# RF_Amplifier.net
KiCad netlist of a schematic drawn in Altium Designer
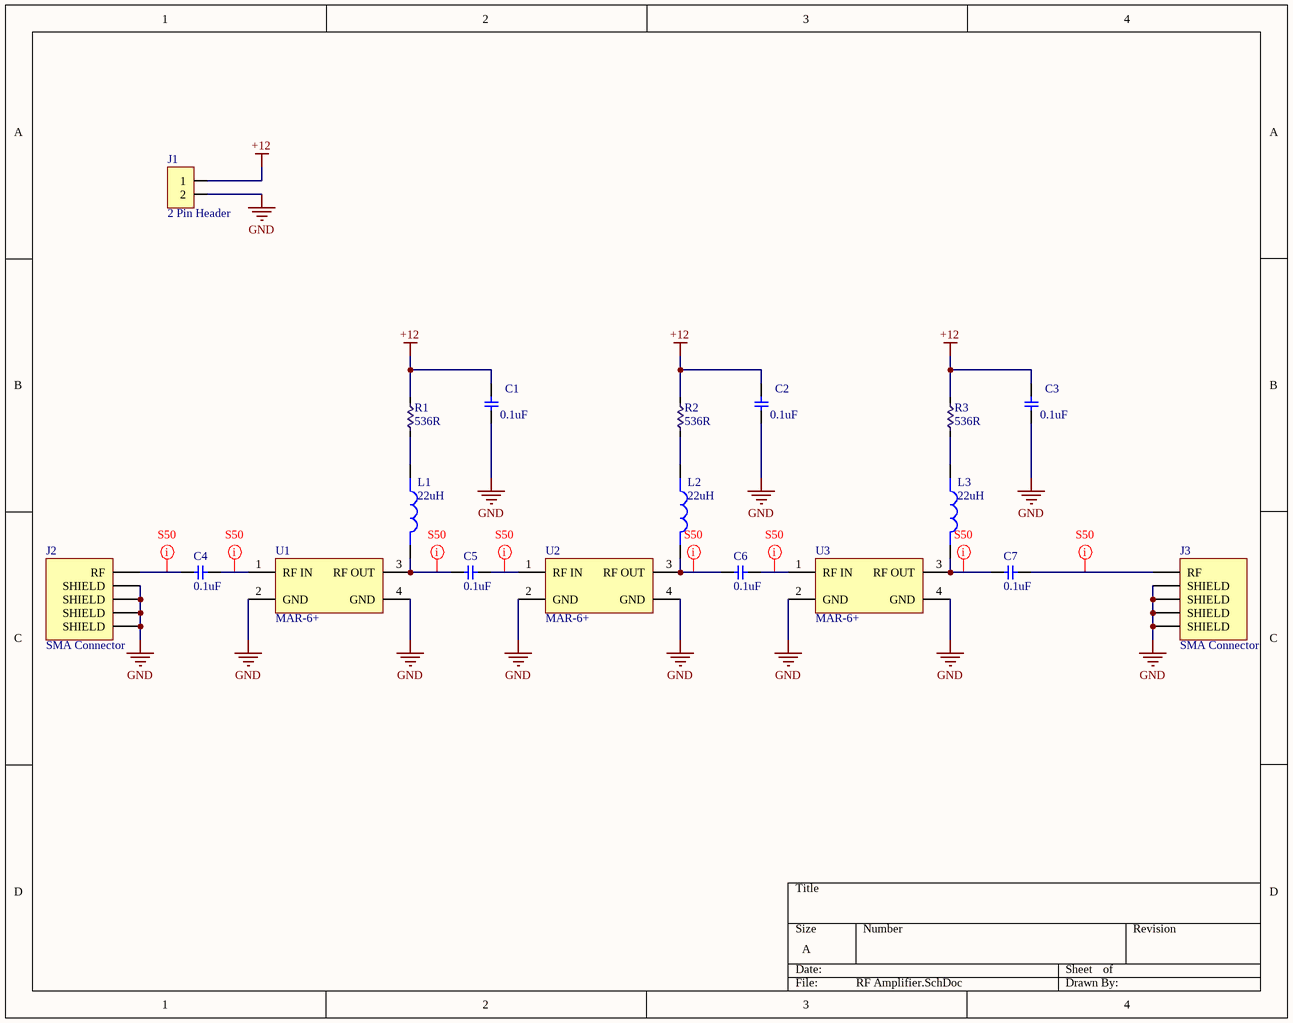
[diagram p0: RF Amplifier.SchDoc]

(export (version "E")
  (design (tool "Eeschema 10.0.6"))
  (components
    (comp (ref "C1") (value "0.1uF") (footprint "CAP805") (libsource (lib "Schlib1") (part "Cap")))
    (comp (ref "C2") (value "0.1uF") (footprint "CAP805") (libsource (lib "Schlib1") (part "Cap")))
    (comp (ref "C3") (value "0.1uF") (footprint "CAP805") (libsource (lib "Schlib1") (part "Cap")))
    (comp (ref "C4") (value "0.1uF") (footprint "CAP805") (libsource (lib "Schlib1") (part "Cap")))
    (comp (ref "C5") (value "0.1uF") (footprint "CAP805") (libsource (lib "Schlib1") (part "Cap")))
    (comp (ref "C6") (value "0.1uF") (footprint "CAP805") (libsource (lib "Schlib1") (part "Cap")))
    (comp (ref "C7") (value "0.1uF") (footprint "CAP805") (libsource (lib "Schlib1") (part "Cap")))
    (comp (ref "J1")
      (value "2 Pin Header")
      (footprint "Connector_2POS_2.54mm")
      (libsource (lib "Schematic_Library") (part "2 Pin Header"))
    )
    (comp (ref "J2")
      (value "SMA Connector")
      (footprint "Molex 73251-1150")
      (libsource (lib "Schematic_Library") (part "SMA Connector"))
    )
    (comp (ref "J3")
      (value "SMA Connector")
      (footprint "Molex 73251-1150")
      (libsource (lib "") (part "SMA Connector_1"))
    )
    (comp (ref "L1")
      (value "22uH")
      (footprint "INDUCtOR_SMD_4.2x4.4")
      (libsource (lib "Schlib1") (part "Inductor"))
    )
    (comp (ref "L2")
      (value "22uH")
      (footprint "INDUCtOR_SMD_4.2x4.4")
      (libsource (lib "Schlib1") (part "Inductor"))
    )
    (comp (ref "L3")
      (value "22uH")
      (footprint "INDUCtOR_SMD_4.2x4.4")
      (libsource (lib "Schlib1") (part "Inductor"))
    )
    (comp (ref "R1") (value "536R") (footprint "RES1812") (libsource (lib "Schlib1") (part "Res")))
    (comp (ref "R2") (value "536R") (footprint "RES1812") (libsource (lib "Schlib1") (part "Res")))
    (comp (ref "R3") (value "536R") (footprint "RES1812") (libsource (lib "Schlib1") (part "Res")))
    (comp (ref "U1") (value "MAR-6+") (footprint "VV105") (libsource (lib "Schlib1") (part "MAR-6+")))
    (comp (ref "U2") (value "MAR-6+") (footprint "VV105") (libsource (lib "Schlib1") (part "MAR-6+")))
    (comp (ref "U3") (value "MAR-6+") (footprint "VV105") (libsource (lib "Schlib1") (part "MAR-6+")))
  )
  (nets
    (net (code "1") (name "+12") (class "Default")
      (node (ref "C1") (pin "2") (pinfunction "2_2") (pintype "passive"))
      (node (ref "C2") (pin "2") (pinfunction "2_2") (pintype "passive"))
      (node (ref "C3") (pin "2") (pinfunction "2_2") (pintype "passive"))
      (node (ref "J1") (pin "1") (pinfunction "1_1") (pintype "passive"))
      (node (ref "R1") (pin "2") (pinfunction "2_2") (pintype "passive"))
      (node (ref "R2") (pin "2") (pinfunction "2_2") (pintype "passive"))
      (node (ref "R3") (pin "2") (pinfunction "2_2") (pintype "passive"))
    )
    (net (code "2") (name "GND") (class "Default")
      (node (ref "C1") (pin "1") (pinfunction "1_1") (pintype "passive"))
      (node (ref "C2") (pin "1") (pinfunction "1_1") (pintype "passive"))
      (node (ref "C3") (pin "1") (pinfunction "1_1") (pintype "passive"))
      (node (ref "J1") (pin "2") (pinfunction "2_2") (pintype "passive"))
      (node (ref "J2") (pin "2") (pinfunction "SHIELD_2") (pintype "passive"))
      (node (ref "J2") (pin "3") (pinfunction "SHIELD_3") (pintype "passive"))
      (node (ref "J2") (pin "4") (pinfunction "SHIELD_4") (pintype "passive"))
      (node (ref "J2") (pin "5") (pinfunction "SHIELD_5") (pintype "passive"))
      (node (ref "J3") (pin "2") (pinfunction "SHIELD_2") (pintype "passive"))
      (node (ref "J3") (pin "3") (pinfunction "SHIELD_3") (pintype "passive"))
      (node (ref "J3") (pin "4") (pinfunction "SHIELD_4") (pintype "passive"))
      (node (ref "J3") (pin "5") (pinfunction "SHIELD_5") (pintype "passive"))
      (node (ref "U1") (pin "2") (pinfunction "GND_2") (pintype "passive"))
      (node (ref "U1") (pin "4") (pinfunction "GND_4") (pintype "passive"))
      (node (ref "U2") (pin "2") (pinfunction "GND_2") (pintype "passive"))
      (node (ref "U2") (pin "4") (pinfunction "GND_4") (pintype "passive"))
      (node (ref "U3") (pin "2") (pinfunction "GND_2") (pintype "passive"))
      (node (ref "U3") (pin "4") (pinfunction "GND_4") (pintype "passive"))
    )
    (net (code "3") (name "Net-(J2-RF)") (class "Default")
      (node (ref "C4") (pin "1") (pinfunction "1_1") (pintype "passive"))
      (node (ref "J2") (pin "1") (pinfunction "RF_1") (pintype "passive"))
    )
    (net (code "4") (name "Net-(J3-RF)") (class "Default")
      (node (ref "C7") (pin "2") (pinfunction "2_2") (pintype "passive"))
      (node (ref "J3") (pin "1") (pinfunction "RF_1") (pintype "passive"))
    )
    (net (code "5") (name "Net-(L1-Pad1)") (class "Default")
      (node (ref "L1") (pin "1") (pinfunction "1_1") (pintype "passive"))
      (node (ref "R1") (pin "1") (pinfunction "1_1") (pintype "passive"))
    )
    (net (code "6") (name "Net-(L2-Pad1)") (class "Default")
      (node (ref "L2") (pin "1") (pinfunction "1_1") (pintype "passive"))
      (node (ref "R2") (pin "1") (pinfunction "1_1") (pintype "passive"))
    )
    (net (code "7") (name "Net-(L3-Pad1)") (class "Default")
      (node (ref "L3") (pin "1") (pinfunction "1_1") (pintype "passive"))
      (node (ref "R3") (pin "1") (pinfunction "1_1") (pintype "passive"))
    )
    (net (code "8") (name "Net-(U1-RF_IN)") (class "Default")
      (node (ref "C4") (pin "2") (pinfunction "2_2") (pintype "passive"))
      (node (ref "U1") (pin "1") (pinfunction "RF_IN_1") (pintype "passive"))
    )
    (net (code "9") (name "Net-(U1-RF_OUT)") (class "Default")
      (node (ref "C5") (pin "1") (pinfunction "1_1") (pintype "passive"))
      (node (ref "L1") (pin "2") (pinfunction "2_2") (pintype "passive"))
      (node (ref "U1") (pin "3") (pinfunction "RF_OUT_3") (pintype "passive"))
    )
    (net (code "10") (name "Net-(U2-RF_IN)") (class "Default")
      (node (ref "C5") (pin "2") (pinfunction "2_2") (pintype "passive"))
      (node (ref "U2") (pin "1") (pinfunction "RF_IN_1") (pintype "passive"))
    )
    (net (code "11") (name "Net-(U2-RF_OUT)") (class "Default")
      (node (ref "C6") (pin "1") (pinfunction "1_1") (pintype "passive"))
      (node (ref "L2") (pin "2") (pinfunction "2_2") (pintype "passive"))
      (node (ref "U2") (pin "3") (pinfunction "RF_OUT_3") (pintype "passive"))
    )
    (net (code "12") (name "Net-(U3-RF_IN)") (class "Default")
      (node (ref "C6") (pin "2") (pinfunction "2_2") (pintype "passive"))
      (node (ref "U3") (pin "1") (pinfunction "RF_IN_1") (pintype "passive"))
    )
    (net (code "13") (name "Net-(U3-RF_OUT)") (class "Default")
      (node (ref "C7") (pin "1") (pinfunction "1_1") (pintype "passive"))
      (node (ref "L3") (pin "2") (pinfunction "2_2") (pintype "passive"))
      (node (ref "U3") (pin "3") (pinfunction "RF_OUT_3") (pintype "passive"))
    )
  )
)
